# Sheet2.net
KiCad netlist of a schematic drawn in Altium Designer
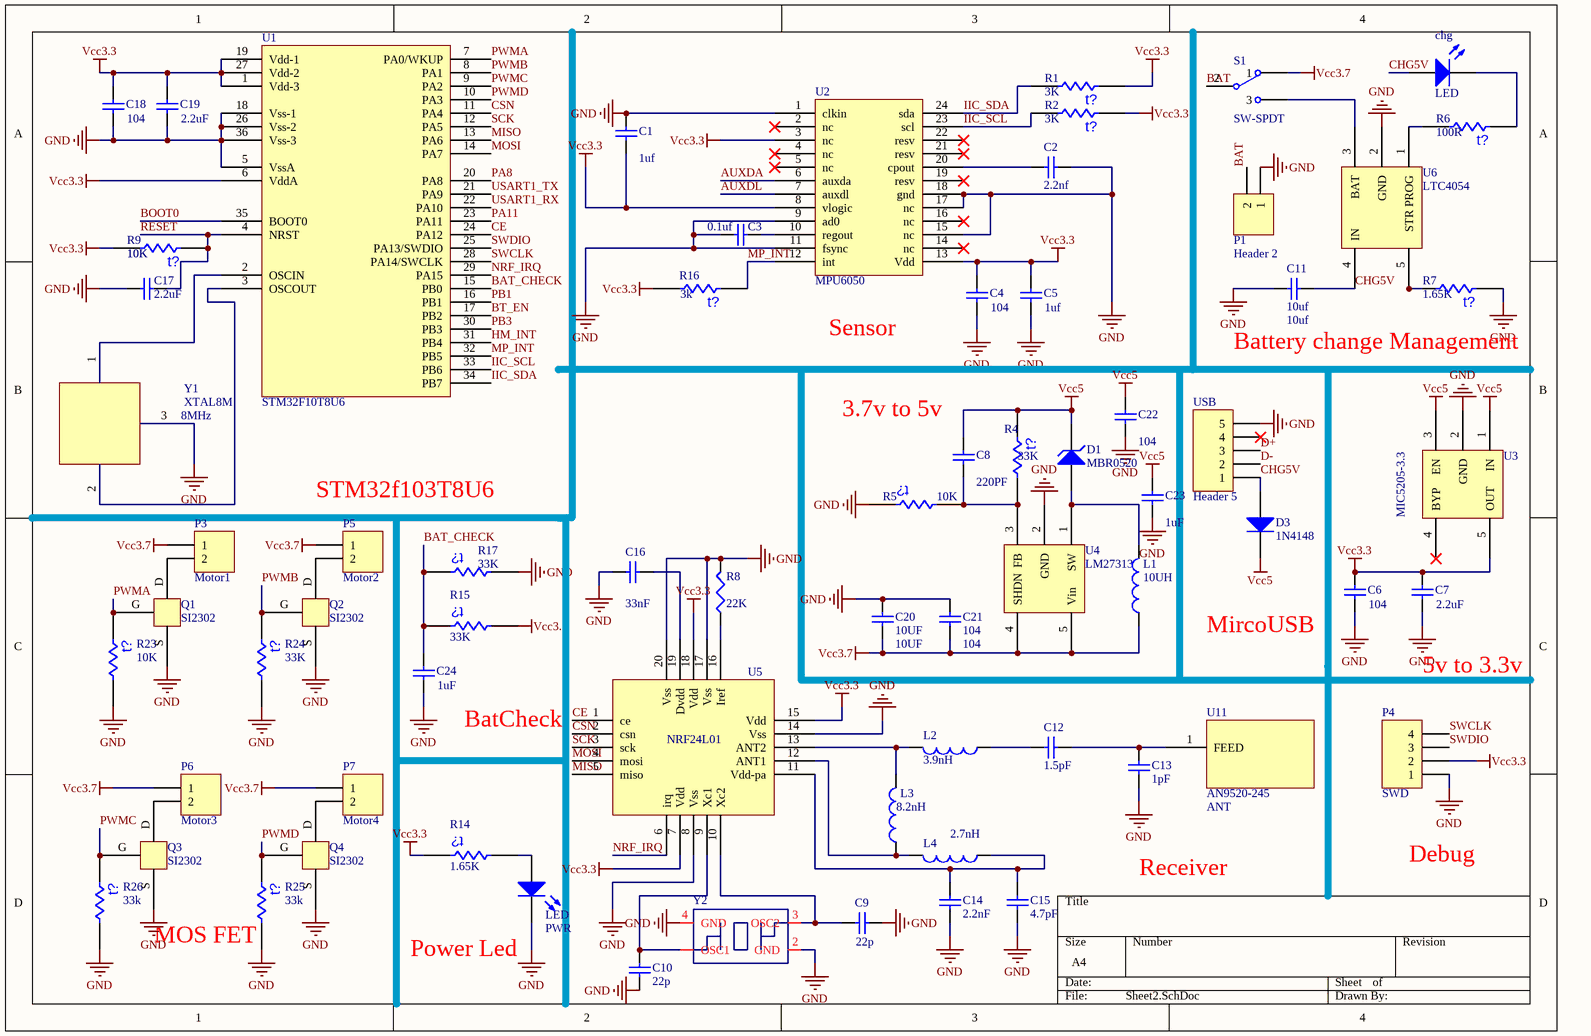
[diagram p0: Sheet2.SchDoc]

(export (version "E")
  (design (tool "Eeschema 10.0.6"))
  (components
    (comp (ref "C1")
      (value "1uf")
      (footprint "1608[0603]")
      (description "Capacitor (Semiconductor SIM Model)")
      (fields (field (name "PUBLISHER") "Altium Limited"))
      (libsource (lib "Miscellaneous Devices") (part "Cap Semi"))
    )
    (comp (ref "C2")
      (value "2.2nf")
      (footprint "1608[0603]")
      (description "Capacitor (Semiconductor SIM Model)")
      (fields (field (name "PUBLISHER") "Altium Limited"))
      (libsource (lib "Miscellaneous Devices") (part "Cap Semi"))
    )
    (comp (ref "C3")
      (value "0.1uf")
      (footprint "1608[0603]")
      (description "Capacitor (Semiconductor SIM Model)")
      (fields (field (name "PUBLISHER") "Altium Limited"))
      (libsource (lib "Miscellaneous Devices") (part "Cap Semi"))
    )
    (comp (ref "C4")
      (value "104")
      (footprint "1608[0603]")
      (description "Capacitor (Semiconductor SIM Model)")
      (fields (field (name "PUBLISHER") "Altium Limited"))
      (libsource (lib "Miscellaneous Devices") (part "Cap Semi"))
    )
    (comp (ref "C5")
      (value "1uf")
      (footprint "1608[0603]")
      (description "Capacitor (Semiconductor SIM Model)")
      (fields (field (name "PUBLISHER") "Altium Limited"))
      (libsource (lib "Miscellaneous Devices") (part "Cap Semi"))
    )
    (comp (ref "C6")
      (value "104")
      (footprint "1608[0603]")
      (description "Capacitor (Semiconductor SIM Model)")
      (fields (field (name "PUBLISHER") "Altium Limited"))
      (libsource (lib "Miscellaneous Devices") (part "Cap Semi"))
    )
    (comp (ref "C7")
      (value "2.2uF")
      (footprint "1608[0603]")
      (description "Capacitor (Semiconductor SIM Model)")
      (fields (field (name "PUBLISHER") "Altium Limited"))
      (libsource (lib "Miscellaneous Devices") (part "Cap Semi"))
    )
    (comp (ref "C8")
      (value "220PF")
      (footprint "1608[0603]")
      (description "Capacitor (Semiconductor SIM Model)")
      (fields (field (name "PUBLISHER") "Altium Limited"))
      (libsource (lib "Miscellaneous Devices") (part "Cap Semi"))
    )
    (comp (ref "C9")
      (value "22p")
      (footprint "1608[0603]")
      (description "Capacitor (Semiconductor SIM Model)")
      (fields (field (name "PUBLISHER") "Altium Limited"))
      (libsource (lib "Miscellaneous Devices") (part "Cap Semi"))
    )
    (comp (ref "C10")
      (value "22p")
      (footprint "1608[0603]")
      (description "Capacitor (Semiconductor SIM Model)")
      (fields (field (name "PUBLISHER") "Altium Limited"))
      (libsource (lib "Miscellaneous Devices") (part "Cap Semi"))
    )
    (comp (ref "C11")
      (value "10uf")
      (footprint "1608[0603]")
      (description "Capacitor (Semiconductor SIM Model)")
      (fields (field (name "ALTIUM_VALUE") "10uf") (field (name "PUBLISHER") "Altium Limited"))
      (libsource (lib "Miscellaneous Devices") (part "Cap Semi"))
    )
    (comp (ref "C12")
      (value "1.5pF")
      (footprint "1608[0603]")
      (description "Capacitor (Semiconductor SIM Model)")
      (fields (field (name "PUBLISHER") "Altium Limited"))
      (libsource (lib "Miscellaneous Devices") (part "Cap Semi"))
    )
    (comp (ref "C13")
      (value "1pF")
      (footprint "1608[0603]")
      (description "Capacitor (Semiconductor SIM Model)")
      (fields (field (name "PUBLISHER") "Altium Limited"))
      (libsource (lib "Miscellaneous Devices") (part "Cap Semi"))
    )
    (comp (ref "C14")
      (value "2.2nF")
      (footprint "1608[0603]")
      (description "Capacitor (Semiconductor SIM Model)")
      (fields (field (name "PUBLISHER") "Altium Limited"))
      (libsource (lib "Miscellaneous Devices") (part "Cap Semi"))
    )
    (comp (ref "C15")
      (value "4.7pF")
      (footprint "1608[0603]")
      (description "Capacitor (Semiconductor SIM Model)")
      (fields (field (name "PUBLISHER") "Altium Limited"))
      (libsource (lib "Miscellaneous Devices") (part "Cap Semi"))
    )
    (comp (ref "C16")
      (value "33nF")
      (footprint "1608[0603]")
      (description "Capacitor (Semiconductor SIM Model)")
      (fields (field (name "PUBLISHER") "Altium Limited"))
      (libsource (lib "Miscellaneous Devices") (part "Cap Semi"))
    )
    (comp (ref "C17")
      (value "2.2uF")
      (footprint "1608[0603]")
      (description "Capacitor (Semiconductor SIM Model)")
      (fields (field (name "PUBLISHER") "Altium Limited"))
      (libsource (lib "Miscellaneous Devices") (part "Cap Semi"))
    )
    (comp (ref "C18")
      (value "104")
      (footprint "1608[0603]")
      (description "Capacitor (Semiconductor SIM Model)")
      (fields (field (name "PUBLISHER") "Altium Limited"))
      (libsource (lib "Miscellaneous Devices") (part "Cap Semi"))
    )
    (comp (ref "C19")
      (value "2.2uF")
      (footprint "1608[0603]")
      (description "Capacitor (Semiconductor SIM Model)")
      (fields (field (name "PUBLISHER") "Altium Limited"))
      (libsource (lib "Miscellaneous Devices") (part "Cap Semi"))
    )
    (comp (ref "C20")
      (value "10UF")
      (footprint "1608[0603]")
      (description "Capacitor (Semiconductor SIM Model)")
      (fields (field (name "ALTIUM_VALUE") "10UF") (field (name "PUBLISHER") "Altium Limited"))
      (libsource (lib "Miscellaneous Devices") (part "Cap Semi"))
    )
    (comp (ref "C21")
      (value "104")
      (footprint "1608[0603]")
      (description "Capacitor (Semiconductor SIM Model)")
      (fields (field (name "ALTIUM_VALUE") "104") (field (name "PUBLISHER") "Altium Limited"))
      (libsource (lib "Miscellaneous Devices") (part "Cap Semi"))
    )
    (comp (ref "C22")
      (value "104")
      (footprint "1608[0603]")
      (description "Capacitor (Semiconductor SIM Model)")
      (fields (field (name "PUBLISHER") "Altium Limited"))
      (libsource (lib "Miscellaneous Devices") (part "Cap Semi"))
    )
    (comp (ref "C23")
      (value "1uF")
      (footprint "1608[0603]")
      (description "Capacitor (Semiconductor SIM Model)")
      (fields (field (name "PUBLISHER") "Altium Limited"))
      (libsource (lib "Miscellaneous Devices") (part "Cap Semi"))
    )
    (comp (ref "C24")
      (value "1uF")
      (footprint "1608[0603]")
      (description "Capacitor (Semiconductor SIM Model)")
      (fields (field (name "PUBLISHER") "Altium Limited"))
      (libsource (lib "Miscellaneous Devices") (part "Cap Semi"))
    )
    (comp (ref "chg")
      (value "LED")
      (footprint "6-0805_N")
      (description "Typical RED, GREEN, YELLOW, AMBER GaAs LED")
      (fields (field (name "PUBLISHER") "Altium Limited"))
      (libsource (lib "Miscellaneous Devices") (part "LED2"))
    )
    (comp (ref "D1")
      (value "MBR0520")
      (footprint "CAPCP5113X06N")
      (description "Zener Diode")
      (fields (field (name "PUBLISHER") "Altium Limited"))
      (libsource (lib "Miscellaneous Devices") (part "D Zener"))
    )
    (comp (ref "D3")
      (value "1N4148")
      (footprint "6-0805_N")
      (description "Default Diode")
      (fields (field (name "PUBLISHER") "Altium Limited"))
      (libsource (lib "Miscellaneous Devices") (part "Diode"))
    )
    (comp (ref "L1")
      (value "10UH")
      (footprint "INDC3035X06N")
      (description "Inductor")
      (fields (field (name "PUBLISHER") "Altium Limited"))
      (libsource (lib "Miscellaneous Devices") (part "Inductor"))
    )
    (comp (ref "L2")
      (value "3.9nH")
      (footprint "0805")
      (description "Inductor")
      (fields (field (name "PUBLISHER") "Altium Limited"))
      (libsource (lib "Miscellaneous Devices") (part "Inductor"))
    )
    (comp (ref "L3")
      (value "8.2nH")
      (footprint "0805")
      (description "Inductor")
      (fields (field (name "PUBLISHER") "Altium Limited"))
      (libsource (lib "Miscellaneous Devices") (part "Inductor"))
    )
    (comp (ref "L4")
      (value "2.7nH")
      (footprint "0805")
      (description "Inductor")
      (fields (field (name "PUBLISHER") "Altium Limited"))
      (libsource (lib "Miscellaneous Devices") (part "Inductor"))
    )
    (comp (ref "P1")
      (value "Header 2")
      (footprint "HDR1X2")
      (description "Header, 2-Pin")
      (fields (field (name "PUBLISHER") "Altium Limited"))
      (libsource (lib "Miscellaneous Connectors") (part "Header 2"))
    )
    (comp (ref "P3")
      (value "Motor1")
      (footprint "MHDR1X2")
      (description "Header, 2-Pin")
      (fields (field (name "PUBLISHER") "Altium Limited"))
      (libsource (lib "Miscellaneous Connectors") (part "MHDR1X2"))
    )
    (comp (ref "P4")
      (value "SWD")
      (footprint "HDR1X4")
      (description "Header, 4-Pin")
      (fields (field (name "PUBLISHER") "Altium Limited"))
      (libsource (lib "Miscellaneous Connectors") (part "Header 4"))
    )
    (comp (ref "P5")
      (value "Motor2")
      (footprint "MHDR1X2")
      (description "Header, 2-Pin")
      (fields (field (name "PUBLISHER") "Altium Limited"))
      (libsource (lib "Miscellaneous Connectors") (part "MHDR1X2"))
    )
    (comp (ref "P6")
      (value "Motor3")
      (footprint "MHDR1X2")
      (description "Header, 2-Pin")
      (fields (field (name "PUBLISHER") "Altium Limited"))
      (libsource (lib "Miscellaneous Connectors") (part "MHDR1X2"))
    )
    (comp (ref "P7")
      (value "Motor4")
      (footprint "MHDR1X2")
      (description "Header, 2-Pin")
      (fields (field (name "PUBLISHER") "Altium Limited"))
      (libsource (lib "Miscellaneous Connectors") (part "MHDR1X2"))
    )
    (comp (ref "PWR")
      (value "LED")
      (footprint "6-0805_N")
      (description "Typical RED, GREEN, YELLOW, AMBER GaAs LED")
      (fields (field (name "PUBLISHER") "Altium Limited"))
      (libsource (lib "Miscellaneous Devices") (part "LED2"))
    )
    (comp (ref "Q1") (value "SI2302") (footprint "SOT23_M") (libsource (lib "Q") (part "Component_1")))
    (comp (ref "Q2") (value "SI2302") (footprint "SOT23_M") (libsource (lib "Q") (part "Component_1")))
    (comp (ref "Q3") (value "SI2302") (footprint "SOT23_M") (libsource (lib "Q") (part "Component_1")))
    (comp (ref "Q4") (value "SI2302") (footprint "SOT23_M") (libsource (lib "Q") (part "Component_1")))
    (comp (ref "R1")
      (value "3K")
      (footprint "6-0805_N")
      (fields (field (name "PUBLISHER") "Altium Limited"))
      (libsource (lib "Miscellaneous Devices") (part "Res Thermal"))
    )
    (comp (ref "R2")
      (value "3K")
      (footprint "6-0805_N")
      (fields (field (name "PUBLISHER") "Altium Limited"))
      (libsource (lib "Miscellaneous Devices") (part "Res Thermal"))
    )
    (comp (ref "R4")
      (value "33K")
      (footprint "6-0805_N")
      (fields (field (name "PUBLISHER") "Altium Limited"))
      (libsource (lib "Miscellaneous Devices") (part "Res Thermal"))
    )
    (comp (ref "R5")
      (value "10K")
      (footprint "6-0805_N")
      (fields (field (name "PUBLISHER") "Altium Limited"))
      (libsource (lib "Miscellaneous Devices") (part "Res Thermal"))
    )
    (comp (ref "R6")
      (value "100R")
      (footprint "6-0805_N")
      (fields (field (name "PUBLISHER") "Altium Limited"))
      (libsource (lib "Miscellaneous Devices") (part "Res Thermal"))
    )
    (comp (ref "R7")
      (value "1.65K")
      (footprint "6-0805_N")
      (fields (field (name "PUBLISHER") "Altium Limited"))
      (libsource (lib "Miscellaneous Devices") (part "Res Thermal"))
    )
    (comp (ref "R8")
      (value "22K")
      (footprint "0805")
      (description "Resistor")
      (fields (field (name "PUBLISHER") "Altium Limited"))
      (libsource (lib "Miscellaneous Devices") (part "Res3"))
    )
    (comp (ref "R9")
      (value "10K")
      (footprint "6-0805_N")
      (fields (field (name "ALTIUM_VALUE") "10K") (field (name "PUBLISHER") "Altium Limited"))
      (libsource (lib "Miscellaneous Devices") (part "Res Thermal"))
    )
    (comp (ref "R14")
      (value "1.65K")
      (footprint "6-0805_N")
      (fields (field (name "PUBLISHER") "Altium Limited"))
      (libsource (lib "Miscellaneous Devices") (part "Res Thermal"))
    )
    (comp (ref "R15")
      (value "33K")
      (footprint "6-0805_N")
      (fields (field (name "PUBLISHER") "Altium Limited"))
      (libsource (lib "Miscellaneous Devices") (part "Res Thermal"))
    )
    (comp (ref "R16")
      (value "3k")
      (footprint "6-0805_N")
      (fields (field (name "PUBLISHER") "Altium Limited"))
      (libsource (lib "Miscellaneous Devices") (part "Res Thermal"))
    )
    (comp (ref "R17")
      (value "33K")
      (footprint "6-0805_N")
      (fields (field (name "PUBLISHER") "Altium Limited"))
      (libsource (lib "Miscellaneous Devices") (part "Res Thermal"))
    )
    (comp (ref "R23")
      (value "10K")
      (footprint "6-0805_N")
      (fields (field (name "PUBLISHER") "Altium Limited"))
      (libsource (lib "Miscellaneous Devices") (part "Res Thermal"))
    )
    (comp (ref "R24")
      (value "33K")
      (footprint "6-0805_N")
      (fields (field (name "PUBLISHER") "Altium Limited"))
      (libsource (lib "Miscellaneous Devices") (part "Res Thermal"))
    )
    (comp (ref "R25")
      (value "33k")
      (footprint "6-0805_N")
      (fields (field (name "PUBLISHER") "Altium Limited"))
      (libsource (lib "Miscellaneous Devices") (part "Res Thermal"))
    )
    (comp (ref "R26")
      (value "33k")
      (footprint "6-0805_N")
      (fields (field (name "PUBLISHER") "Altium Limited"))
      (libsource (lib "Miscellaneous Devices") (part "Res Thermal"))
    )
    (comp (ref "S1")
      (value "SW-SPDT")
      (footprint "HDR2X3")
      (description "SPDT Subminiature Toggle Switch, Right Angle Mounting, Vertical Actuation")
      (fields (field (name "PUBLISHER") "Altium Limited"))
      (libsource (lib "四轴") (part "SW-SPDT"))
    )
    (comp (ref "U1")
      (value "STM32F10T8U6")
      (footprint "stm32f1038tu6")
      (libsource (lib "stm32") (part "STM32F10T8U6"))
    )
    (comp (ref "U2") (value "MPU6050") (footprint "U8") (libsource (lib "stm32") (part "MPU6050")))
    (comp (ref "U3")
      (value "MIC5205-3.3")
      (footprint "SOT95P280X120-5N")
      (libsource (lib "stm32") (part "MIC5205-3.3"))
    )
    (comp (ref "U4")
      (value "LM27313")
      (footprint "SOT95P280X120-5N")
      (libsource (lib "stm32") (part "LM27313"))
    )
    (comp (ref "U5")
      (value "NRF24L01")
      (footprint "QFN-ML20_L")
      (libsource (lib "NRF24L01") (part "Component_1"))
    )
    (comp (ref "U6")
      (value "LTC4054")
      (footprint "SOT95P280X120-5N")
      (libsource (lib "stm32") (part "LTC4054"))
    )
    (comp (ref "U11") (value "ANT") (footprint "AN9520-245") (libsource (lib "ANT1") (part "Component_1")))
    (comp (ref "USB")
      (value "Header 5")
      (footprint "USB_MICRO_B")
      (description "Header, 5-Pin")
      (fields (field (name "PUBLISHER") "Altium Limited"))
      (libsource (lib "Miscellaneous Connectors") (part "Header 5"))
    )
    (comp (ref "Y1")
      (value "XTAL8M")
      (footprint "CAPC1219X07N")
      (fields (field (name "ALTIUM_VALUE") "8MHz"))
      (libsource (lib "stm32") (part "XTAL8M"))
    )
    (comp (ref "Y2")
      (value "Component_1")
      (footprint "XTAL16MHz")
      (libsource (lib "XTAL") (part "Component_1"))
    )
  )
  (nets
    (net (code "3") (name "/AUXDA") (class "Default")
      (node (ref "U2") (pin "6") (pinfunction "auxda_6") (pintype "passive"))
    )
    (net (code "4") (name "/AUXDL") (class "Default")
      (node (ref "U2") (pin "7") (pinfunction "auxdl_7") (pintype "passive"))
    )
    (net (code "5") (name "/BAT") (class "Default")
      (node (ref "P1") (pin "2") (pinfunction "2_2") (pintype "passive"))
      (node (ref "S1") (pin "2") (pinfunction "2_2") (pintype "passive"))
    )
    (net (code "6") (name "/BAT_CHECK") (class "Default")
      (node (ref "C24") (pin "1") (pinfunction "1_1") (pintype "passive"))
      (node (ref "R15") (pin "1") (pinfunction "1_1") (pintype "passive"))
      (node (ref "R17") (pin "1") (pinfunction "1_1") (pintype "passive"))
      (node (ref "U1") (pin "15") (pinfunction "PB0_15") (pintype "passive"))
    )
    (net (code "7") (name "/BOOT0") (class "Default")
      (node (ref "U1") (pin "35") (pinfunction "BOOT0_35") (pintype "passive"))
    )
    (net (code "8") (name "/BT_EN") (class "Default")
      (node (ref "U1") (pin "17") (pinfunction "PB2_17") (pintype "passive"))
    )
    (net (code "11") (name "/CE") (class "Default")
      (node (ref "U1") (pin "24") (pinfunction "PA12_24") (pintype "passive"))
      (node (ref "U5") (pin "1") (pinfunction "ce_1") (pintype "passive"))
    )
    (net (code "12") (name "/CHG5V") (class "Default")
      (node (ref "C11") (pin "1") (pinfunction "1_1") (pintype "passive"))
      (node (ref "D3") (pin "1") (pinfunction "A_1") (pintype "passive"))
      (node (ref "U6") (pin "4") (pinfunction "IN_4") (pintype "passive"))
      (node (ref "USB") (pin "1") (pinfunction "1_1") (pintype "passive"))
      (node (ref "chg") (pin "1") (pinfunction "A_1") (pintype "passive"))
    )
    (net (code "13") (name "/CSN") (class "Default")
      (node (ref "U1") (pin "11") (pinfunction "PA4_11") (pintype "passive"))
      (node (ref "U5") (pin "2") (pinfunction "csn_2") (pintype "passive"))
    )
    (net (code "14") (name "/D+") (class "Default")
      (node (ref "USB") (pin "3") (pinfunction "3_3") (pintype "passive"))
    )
    (net (code "15") (name "/D-") (class "Default")
      (node (ref "USB") (pin "2") (pinfunction "2_2") (pintype "passive"))
    )
    (net (code "17") (name "/HM_INT") (class "Default")
      (node (ref "U1") (pin "31") (pinfunction "PB4_31") (pintype "passive"))
    )
    (net (code "18") (name "/IIC_SCL") (class "Default")
      (node (ref "R2") (pin "2") (pinfunction "2_2") (pintype "passive"))
      (node (ref "U1") (pin "33") (pinfunction "PB6_33") (pintype "passive"))
      (node (ref "U2") (pin "23") (pinfunction "scl_23") (pintype "passive"))
    )
    (net (code "19") (name "/IIC_SDA") (class "Default")
      (node (ref "R1") (pin "2") (pinfunction "2_2") (pintype "passive"))
      (node (ref "U1") (pin "34") (pinfunction "PB7_34") (pintype "passive"))
      (node (ref "U2") (pin "24") (pinfunction "sda_24") (pintype "passive"))
    )
    (net (code "20") (name "/MISO") (class "Default")
      (node (ref "U1") (pin "13") (pinfunction "PA6_13") (pintype "passive"))
      (node (ref "U5") (pin "5") (pinfunction "miso_5") (pintype "passive"))
    )
    (net (code "22") (name "/MOSI") (class "Default")
      (node (ref "U1") (pin "14") (pinfunction "PA7_14") (pintype "passive"))
      (node (ref "U5") (pin "4") (pinfunction "mosi_4") (pintype "passive"))
    )
    (net (code "23") (name "/MP_INT") (class "Default")
      (node (ref "R16") (pin "1") (pinfunction "1_1") (pintype "passive"))
      (node (ref "U1") (pin "32") (pinfunction "PB5_32") (pintype "passive"))
      (node (ref "U2") (pin "12") (pinfunction "int_12") (pintype "passive"))
    )
    (net (code "25") (name "/NRF_IRQ") (class "Default")
      (node (ref "U1") (pin "29") (pinfunction "PA15_29") (pintype "passive"))
      (node (ref "U5") (pin "6") (pinfunction "irq_6") (pintype "passive"))
    )
    (net (code "26") (name "/PA8") (class "Default")
      (node (ref "U1") (pin "20") (pinfunction "PA8_20") (pintype "passive"))
    )
    (net (code "27") (name "/PA11") (class "Default")
      (node (ref "U1") (pin "23") (pinfunction "PA11_23") (pintype "passive"))
    )
    (net (code "28") (name "/PB1") (class "Default")
      (node (ref "U1") (pin "16") (pinfunction "PB1_16") (pintype "passive"))
    )
    (net (code "29") (name "/PB3") (class "Default")
      (node (ref "U1") (pin "30") (pinfunction "PB3_30") (pintype "passive"))
    )
    (net (code "30") (name "/PWMA") (class "Default")
      (node (ref "Q1") (pin "G") (pintype "passive"))
      (node (ref "R23") (pin "1") (pinfunction "1_1") (pintype "passive"))
      (node (ref "U1") (pin "7") (pinfunction "PA0/WKUP_7") (pintype "passive"))
    )
    (net (code "31") (name "/PWMB") (class "Default")
      (node (ref "Q2") (pin "G") (pintype "passive"))
      (node (ref "R24") (pin "1") (pinfunction "1_1") (pintype "passive"))
      (node (ref "U1") (pin "8") (pinfunction "PA1_8") (pintype "passive"))
    )
    (net (code "32") (name "/PWMC") (class "Default")
      (node (ref "Q3") (pin "G") (pintype "passive"))
      (node (ref "R26") (pin "1") (pinfunction "1_1") (pintype "passive"))
      (node (ref "U1") (pin "9") (pinfunction "PA2_9") (pintype "passive"))
    )
    (net (code "33") (name "/PWMD") (class "Default")
      (node (ref "Q4") (pin "G") (pintype "passive"))
      (node (ref "R25") (pin "1") (pinfunction "1_1") (pintype "passive"))
      (node (ref "U1") (pin "10") (pinfunction "PA3_10") (pintype "passive"))
    )
    (net (code "35") (name "/RESET") (class "Default")
      (node (ref "C17") (pin "2") (pinfunction "2_2") (pintype "passive"))
      (node (ref "R9") (pin "1") (pinfunction "1_1") (pintype "passive"))
      (node (ref "U1") (pin "4") (pinfunction "NRST_4") (pintype "passive"))
    )
    (net (code "37") (name "/SCK") (class "Default")
      (node (ref "U1") (pin "12") (pinfunction "PA5_12") (pintype "passive"))
      (node (ref "U5") (pin "3") (pinfunction "sck_3") (pintype "passive"))
    )
    (net (code "39") (name "/SWCLK") (class "Default")
      (node (ref "P4") (pin "4") (pinfunction "4_4") (pintype "passive"))
      (node (ref "U1") (pin "28") (pinfunction "PA14/SWCLK_28") (pintype "passive"))
    )
    (net (code "40") (name "/SWDIO") (class "Default")
      (node (ref "P4") (pin "3") (pinfunction "3_3") (pintype "passive"))
      (node (ref "U1") (pin "25") (pinfunction "PA13/SWDIO_25") (pintype "passive"))
    )
    (net (code "42") (name "/USART1_RX") (class "Default")
      (node (ref "U1") (pin "22") (pinfunction "PA10_22") (pintype "passive"))
    )
    (net (code "43") (name "/USART1_TX") (class "Default")
      (node (ref "U1") (pin "21") (pinfunction "PA9_21") (pintype "passive"))
    )
    (net (code "44") (name "GND") (class "Default")
      (node (ref "C1") (pin "2") (pinfunction "2_2") (pintype "passive"))
      (node (ref "C10") (pin "1") (pinfunction "1_1") (pintype "passive"))
      (node (ref "C11") (pin "2") (pinfunction "2_2") (pintype "passive"))
      (node (ref "C13") (pin "1") (pinfunction "1_1") (pintype "passive"))
      (node (ref "C14") (pin "1") (pinfunction "1_1") (pintype "passive"))
      (node (ref "C15") (pin "1") (pinfunction "1_1") (pintype "passive"))
      (node (ref "C16") (pin "1") (pinfunction "1_1") (pintype "passive"))
      (node (ref "C17") (pin "1") (pinfunction "1_1") (pintype "passive"))
      (node (ref "C18") (pin "1") (pinfunction "1_1") (pintype "passive"))
      (node (ref "C19") (pin "1") (pinfunction "1_1") (pintype "passive"))
      (node (ref "C2") (pin "1") (pinfunction "1_1") (pintype "passive"))
      (node (ref "C20") (pin "1") (pinfunction "1_1") (pintype "passive"))
      (node (ref "C21") (pin "1") (pinfunction "1_1") (pintype "passive"))
      (node (ref "C22") (pin "2") (pinfunction "2_2") (pintype "passive"))
      (node (ref "C23") (pin "2") (pinfunction "2_2") (pintype "passive"))
      (node (ref "C24") (pin "2") (pinfunction "2_2") (pintype "passive"))
      (node (ref "C3") (pin "2") (pinfunction "2_2") (pintype "passive"))
      (node (ref "C4") (pin "2") (pinfunction "2_2") (pintype "passive"))
      (node (ref "C5") (pin "2") (pinfunction "2_2") (pintype "passive"))
      (node (ref "C6") (pin "2") (pinfunction "2_2") (pintype "passive"))
      (node (ref "C7") (pin "2") (pinfunction "2_2") (pintype "passive"))
      (node (ref "C9") (pin "2") (pinfunction "2_2") (pintype "passive"))
      (node (ref "P1") (pin "1") (pinfunction "1_1") (pintype "passive"))
      (node (ref "P4") (pin "1") (pinfunction "1_1") (pintype "passive"))
      (node (ref "PWR") (pin "2") (pinfunction "K_2") (pintype "passive"))
      (node (ref "Q1") (pin "S") (pintype "passive"))
      (node (ref "Q2") (pin "S") (pintype "passive"))
      (node (ref "Q3") (pin "S") (pintype "passive"))
      (node (ref "Q4") (pin "S") (pintype "passive"))
      (node (ref "R17") (pin "2") (pinfunction "2_2") (pintype "passive"))
      (node (ref "R23") (pin "2") (pinfunction "2_2") (pintype "passive"))
      (node (ref "R24") (pin "2") (pinfunction "2_2") (pintype "passive"))
      (node (ref "R25") (pin "2") (pinfunction "2_2") (pintype "passive"))
      (node (ref "R26") (pin "2") (pinfunction "2_2") (pintype "passive"))
      (node (ref "R5") (pin "1") (pinfunction "1_1") (pintype "passive"))
      (node (ref "R7") (pin "1") (pinfunction "1_1") (pintype "passive"))
      (node (ref "R8") (pin "2") (pinfunction "2_2") (pintype "passive"))
      (node (ref "U1") (pin "18") (pinfunction "Vss-1_18") (pintype "passive"))
      (node (ref "U1") (pin "26") (pinfunction "Vss-2_26") (pintype "passive"))
      (node (ref "U1") (pin "36") (pinfunction "Vss-3_36") (pintype "passive"))
      (node (ref "U1") (pin "5") (pinfunction "VssA_5") (pintype "passive"))
      (node (ref "U2") (pin "1") (pinfunction "clkin_1") (pintype "passive"))
      (node (ref "U2") (pin "11") (pinfunction "fsync_11") (pintype "passive"))
      (node (ref "U2") (pin "15") (pinfunction "nc_15") (pintype "passive"))
      (node (ref "U2") (pin "17") (pinfunction "nc_17") (pintype "passive"))
      (node (ref "U2") (pin "18") (pinfunction "gnd_18") (pintype "passive"))
      (node (ref "U2") (pin "9") (pinfunction "ad0_9") (pintype "passive"))
      (node (ref "U3") (pin "2") (pinfunction "GND_2") (pintype "passive"))
      (node (ref "U4") (pin "2") (pinfunction "GND_2") (pintype "passive"))
      (node (ref "U5") (pin "14") (pinfunction "Vss_14") (pintype "passive"))
      (node (ref "U5") (pin "17") (pinfunction "Vss_17") (pintype "passive"))
      (node (ref "U5") (pin "20") (pinfunction "Vss_20") (pintype "passive"))
      (node (ref "U5") (pin "8") (pinfunction "Vss_8") (pintype "passive"))
      (node (ref "U6") (pin "2") (pinfunction "GND_2") (pintype "passive"))
      (node (ref "USB") (pin "5") (pinfunction "5_5") (pintype "passive"))
      (node (ref "Y1") (pin "3") (pinfunction "PA18_3") (pintype "passive"))
      (node (ref "Y2") (pin "2") (pinfunction "GND_2") (pintype "passive"))
      (node (ref "Y2") (pin "4") (pinfunction "GND_4") (pintype "passive"))
    )
    (net (code "45") (name "Net-(C12-Pad2)") (class "Default")
      (node (ref "C12") (pin "2") (pinfunction "2_2") (pintype "passive"))
      (node (ref "L2") (pin "1") (pinfunction "1_1") (pintype "passive"))
    )
    (net (code "46") (name "Net-(D1-A)") (class "Default")
      (node (ref "D1") (pin "1") (pinfunction "A_1") (pintype "passive"))
      (node (ref "L1") (pin "2") (pinfunction "2_2") (pintype "passive"))
      (node (ref "U4") (pin "1") (pinfunction "SW_1") (pintype "passive"))
    )
    (net (code "47") (name "Net-(PWR-A)") (class "Default")
      (node (ref "PWR") (pin "1") (pinfunction "A_1") (pintype "passive"))
      (node (ref "R14") (pin "2") (pinfunction "2_2") (pintype "passive"))
    )
    (net (code "48") (name "Net-(Q1-0)") (class "Default")
      (node (ref "P3") (pin "2") (pinfunction "2_2") (pintype "passive"))
      (node (ref "Q1") (pin "D") (pinfunction "0_D") (pintype "passive"))
    )
    (net (code "49") (name "Net-(Q2-0)") (class "Default")
      (node (ref "P5") (pin "2") (pinfunction "2_2") (pintype "passive"))
      (node (ref "Q2") (pin "D") (pinfunction "0_D") (pintype "passive"))
    )
    (net (code "50") (name "Net-(Q3-0)") (class "Default")
      (node (ref "P6") (pin "2") (pinfunction "2_2") (pintype "passive"))
      (node (ref "Q3") (pin "D") (pinfunction "0_D") (pintype "passive"))
    )
    (net (code "51") (name "Net-(Q4-0)") (class "Default")
      (node (ref "P7") (pin "2") (pinfunction "2_2") (pintype "passive"))
      (node (ref "Q4") (pin "D") (pinfunction "0_D") (pintype "passive"))
    )
    (net (code "52") (name "Net-(R7-Pad2)") (class "Default")
      (node (ref "R7") (pin "2") (pinfunction "2_2") (pintype "passive"))
      (node (ref "U6") (pin "5") (pintype "passive"))
    )
    (net (code "53") (name "Net-(U1-OSCIN)") (class "Default")
      (node (ref "U1") (pin "2") (pinfunction "OSCIN_2") (pintype "passive"))
      (node (ref "Y1") (pin "1") (pinfunction "PA16_1") (pintype "passive"))
    )
    (net (code "54") (name "Net-(U1-OSCOUT)") (class "Default")
      (node (ref "U1") (pin "3") (pinfunction "OSCOUT_3") (pintype "passive"))
      (node (ref "Y1") (pin "2") (pinfunction "PA17_2") (pintype "passive"))
    )
    (net (code "55") (name "Net-(U2-cpout)") (class "Default")
      (node (ref "C2") (pin "2") (pinfunction "2_2") (pintype "passive"))
      (node (ref "U2") (pin "20") (pinfunction "cpout_20") (pintype "passive"))
    )
    (net (code "56") (name "Net-(U2-regout)") (class "Default")
      (node (ref "C3") (pin "1") (pinfunction "1_1") (pintype "passive"))
      (node (ref "U2") (pin "10") (pinfunction "regout_10") (pintype "passive"))
    )
    (net (code "57") (name "Net-(U4-FB)") (class "Default")
      (node (ref "C8") (pin "2") (pinfunction "2_2") (pintype "passive"))
      (node (ref "R4") (pin "2") (pinfunction "2_2") (pintype "passive"))
      (node (ref "R5") (pin "2") (pinfunction "2_2") (pintype "passive"))
      (node (ref "U4") (pin "3") (pinfunction "FB_3") (pintype "passive"))
    )
    (net (code "58") (name "Net-(U5-ANT1)") (class "Default")
      (node (ref "L3") (pin "1") (pinfunction "1_1") (pintype "passive"))
      (node (ref "L4") (pin "2") (pinfunction "2_2") (pintype "passive"))
      (node (ref "U5") (pin "12") (pinfunction "ANT1_12") (pintype "passive"))
    )
    (net (code "59") (name "Net-(U5-ANT2)") (class "Default")
      (node (ref "L2") (pin "2") (pinfunction "2_2") (pintype "passive"))
      (node (ref "L3") (pin "2") (pinfunction "2_2") (pintype "passive"))
      (node (ref "U5") (pin "13") (pinfunction "ANT2_13") (pintype "passive"))
    )
    (net (code "60") (name "Net-(U5-Dvdd)") (class "Default")
      (node (ref "C16") (pin "2") (pinfunction "2_2") (pintype "passive"))
      (node (ref "U5") (pin "19") (pinfunction "Dvdd_19") (pintype "passive"))
    )
    (net (code "61") (name "Net-(U5-Iref)") (class "Default")
      (node (ref "R8") (pin "1") (pinfunction "1_1") (pintype "passive"))
      (node (ref "U5") (pin "16") (pinfunction "Iref_16") (pintype "passive"))
    )
    (net (code "62") (name "Net-(U5-Vdd-pa)") (class "Default")
      (node (ref "C14") (pin "2") (pinfunction "2_2") (pintype "passive"))
      (node (ref "C15") (pin "2") (pinfunction "2_2") (pintype "passive"))
      (node (ref "L4") (pin "1") (pinfunction "1_1") (pintype "passive"))
      (node (ref "U5") (pin "11") (pinfunction "Vdd-pa_11") (pintype "passive"))
    )
    (net (code "63") (name "Net-(U5-Xc1)") (class "Default")
      (node (ref "C10") (pin "2") (pinfunction "2_2") (pintype "passive"))
      (node (ref "U5") (pin "9") (pinfunction "Xc1_9") (pintype "passive"))
      (node (ref "Y2") (pin "1") (pinfunction "OSC1_1") (pintype "passive"))
    )
    (net (code "64") (name "Net-(U5-Xc2)") (class "Default")
      (node (ref "C9") (pin "1") (pinfunction "1_1") (pintype "passive"))
      (node (ref "U5") (pin "10") (pinfunction "Xc2_10") (pintype "passive"))
      (node (ref "Y2") (pin "3") (pinfunction "OSC2_3") (pintype "passive"))
    )
    (net (code "65") (name "Net-(U6-BAT)") (class "Default")
      (node (ref "S1") (pin "3") (pinfunction "3_3") (pintype "passive"))
      (node (ref "U6") (pin "3") (pinfunction "BAT_3") (pintype "passive"))
    )
    (net (code "66") (name "Net-(U6-STR_PROG)") (class "Default")
      (node (ref "R6") (pin "2") (pinfunction "2_2") (pintype "passive"))
      (node (ref "U6") (pin "1") (pinfunction "STR_PROG_1") (pintype "passive"))
    )
    (net (code "67") (name "Net-(U11-FEED)") (class "Default")
      (node (ref "C12") (pin "1") (pinfunction "1_1") (pintype "passive"))
      (node (ref "C13") (pin "2") (pinfunction "2_2") (pintype "passive"))
      (node (ref "U11") (pin "1") (pinfunction "FEED_1") (pintype "passive"))
    )
    (net (code "68") (name "Net-(chg-K)") (class "Default")
      (node (ref "R6") (pin "1") (pinfunction "1_1") (pintype "passive"))
      (node (ref "chg") (pin "2") (pinfunction "K_2") (pintype "passive"))
    )
    (net (code "69") (name "Vcc3.3") (class "Default")
      (node (ref "C1") (pin "1") (pinfunction "1_1") (pintype "passive"))
      (node (ref "C18") (pin "2") (pinfunction "2_2") (pintype "passive"))
      (node (ref "C19") (pin "2") (pinfunction "2_2") (pintype "passive"))
      (node (ref "C4") (pin "1") (pinfunction "1_1") (pintype "passive"))
      (node (ref "C5") (pin "1") (pinfunction "1_1") (pintype "passive"))
      (node (ref "C6") (pin "1") (pinfunction "1_1") (pintype "passive"))
      (node (ref "C7") (pin "1") (pinfunction "1_1") (pintype "passive"))
      (node (ref "P4") (pin "2") (pinfunction "2_2") (pintype "passive"))
      (node (ref "R1") (pin "1") (pinfunction "1_1") (pintype "passive"))
      (node (ref "R14") (pin "1") (pinfunction "1_1") (pintype "passive"))
      (node (ref "R16") (pin "2") (pinfunction "2_2") (pintype "passive"))
      (node (ref "R2") (pin "1") (pinfunction "1_1") (pintype "passive"))
      (node (ref "R9") (pin "2") (pinfunction "2_2") (pintype "passive"))
      (node (ref "U1") (pin "1") (pinfunction "Vdd-3_1") (pintype "passive"))
      (node (ref "U1") (pin "19") (pinfunction "Vdd-1_19") (pintype "passive"))
      (node (ref "U1") (pin "27") (pinfunction "Vdd-2_27") (pintype "passive"))
      (node (ref "U1") (pin "6") (pinfunction "VddA_6") (pintype "passive"))
      (node (ref "U2") (pin "13") (pinfunction "Vdd_13") (pintype "passive"))
      (node (ref "U2") (pin "3") (pinfunction "nc_3") (pintype "passive"))
      (node (ref "U2") (pin "8") (pinfunction "vlogic_8") (pintype "passive"))
      (node (ref "U3") (pin "5") (pinfunction "OUT_5") (pintype "passive"))
      (node (ref "U5") (pin "15") (pinfunction "Vdd_15") (pintype "passive"))
      (node (ref "U5") (pin "18") (pinfunction "Vdd_18") (pintype "passive"))
      (node (ref "U5") (pin "7") (pinfunction "Vdd_7") (pintype "passive"))
    )
    (net (code "70") (name "Vcc3.7") (class "Default")
      (node (ref "C20") (pin "2") (pinfunction "2_2") (pintype "passive"))
      (node (ref "C21") (pin "2") (pinfunction "2_2") (pintype "passive"))
      (node (ref "L1") (pin "1") (pinfunction "1_1") (pintype "passive"))
      (node (ref "P3") (pin "1") (pinfunction "1_1") (pintype "passive"))
      (node (ref "P5") (pin "1") (pinfunction "1_1") (pintype "passive"))
      (node (ref "P6") (pin "1") (pinfunction "1_1") (pintype "passive"))
      (node (ref "P7") (pin "1") (pinfunction "1_1") (pintype "passive"))
      (node (ref "R15") (pin "2") (pinfunction "2_2") (pintype "passive"))
      (node (ref "S1") (pin "1") (pinfunction "1_1") (pintype "passive"))
      (node (ref "U4") (pin "4") (pinfunction "SHDN_4") (pintype "passive"))
      (node (ref "U4") (pin "5") (pinfunction "Vin_5") (pintype "passive"))
    )
    (net (code "71") (name "Vcc5") (class "Default")
      (node (ref "C22") (pin "1") (pinfunction "1_1") (pintype "passive"))
      (node (ref "C23") (pin "1") (pinfunction "1_1") (pintype "passive"))
      (node (ref "C8") (pin "1") (pinfunction "1_1") (pintype "passive"))
      (node (ref "D1") (pin "2") (pinfunction "K_2") (pintype "passive"))
      (node (ref "D3") (pin "2") (pinfunction "K_2") (pintype "passive"))
      (node (ref "R4") (pin "1") (pinfunction "1_1") (pintype "passive"))
      (node (ref "U3") (pin "1") (pinfunction "IN_1") (pintype "passive"))
      (node (ref "U3") (pin "3") (pinfunction "EN_3") (pintype "passive"))
    )
    (net (code "72") (name "unconnected-(U2-nc-Pad2)") (class "Default")
      (node (ref "U2") (pin "2") (pinfunction "nc_2") (pintype "passive+no_connect"))
    )
    (net (code "73") (name "unconnected-(U2-nc-Pad4)") (class "Default")
      (node (ref "U2") (pin "4") (pinfunction "nc_4") (pintype "passive+no_connect"))
    )
    (net (code "74") (name "unconnected-(U2-nc-Pad5)") (class "Default")
      (node (ref "U2") (pin "5") (pinfunction "nc_5") (pintype "passive+no_connect"))
    )
    (net (code "75") (name "unconnected-(U2-nc-Pad14)") (class "Default")
      (node (ref "U2") (pin "14") (pinfunction "nc_14") (pintype "passive+no_connect"))
    )
    (net (code "76") (name "unconnected-(U2-nc-Pad16)") (class "Default")
      (node (ref "U2") (pin "16") (pinfunction "nc_16") (pintype "passive+no_connect"))
    )
    (net (code "77") (name "unconnected-(U2-resv-Pad19)") (class "Default")
      (node (ref "U2") (pin "19") (pinfunction "resv_19") (pintype "passive+no_connect"))
    )
    (net (code "78") (name "unconnected-(U2-resv-Pad21)") (class "Default")
      (node (ref "U2") (pin "21") (pinfunction "resv_21") (pintype "passive+no_connect"))
    )
    (net (code "79") (name "unconnected-(U2-resv-Pad22)") (class "Default")
      (node (ref "U2") (pin "22") (pinfunction "resv_22") (pintype "passive+no_connect"))
    )
    (net (code "80") (name "unconnected-(U3-BYP-Pad4)") (class "Default")
      (node (ref "U3") (pin "4") (pinfunction "BYP_4") (pintype "passive+no_connect"))
    )
    (net (code "81") (name "unconnected-(USB-Pad4)") (class "Default")
      (node (ref "USB") (pin "4") (pinfunction "4_4") (pintype "passive+no_connect"))
    )
  )
)
